# MicroBrute_Noise_add-on.net
KiCad netlist of a schematic drawn in EAGLE
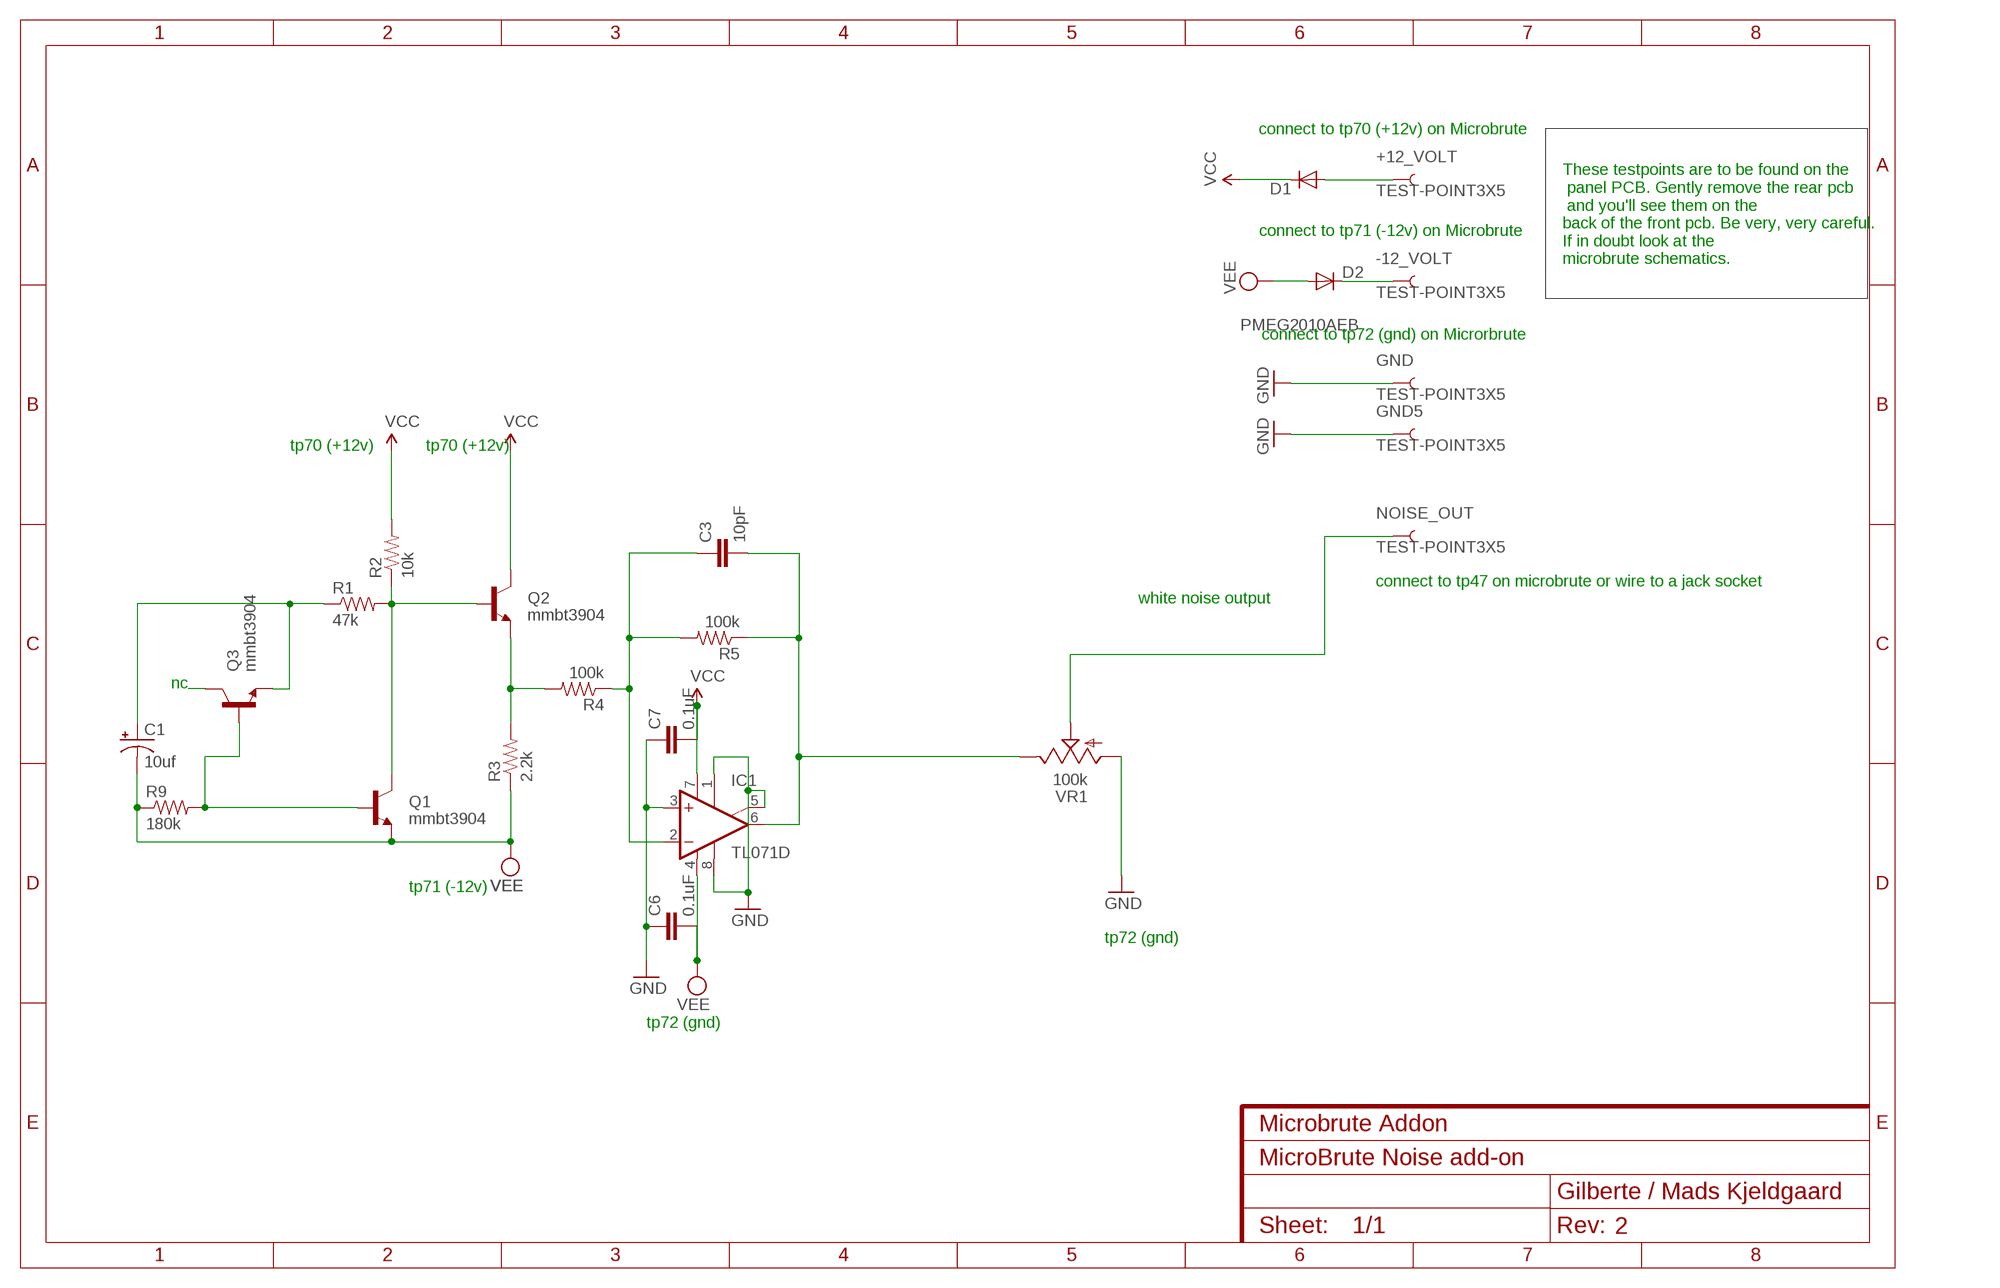
[diagram p0: schematic, sheet 1]

(export (version "E")
  (design (tool "Eeschema 10.0.6"))
  (components
    (comp (ref "+12_VOLT")
      (value "TEST-POINT3X5")
      (footprint "eagle-import:PAD.03X.05")
      (libsource (lib "eagle-import") (part "TEST-POINT3X5"))
    )
    (comp (ref "-12_VOLT")
      (value "TEST-POINT3X5")
      (footprint "eagle-import:PAD.03X.05")
      (libsource (lib "eagle-import") (part "TEST-POINT3X5"))
    )
    (comp (ref "C1")
      (value "10uf")
      (footprint "eagle-import:PANASONIC_C")
      (libsource (lib "eagle-import") (part "CAP_POLC"))
    )
    (comp (ref "C3")
      (value "10pF")
      (footprint "eagle-import:0603-CAP")
      (libsource (lib "eagle-import") (part "0.1UF-25V(+80/-20%)(0603)"))
    )
    (comp (ref "C6")
      (value "0.1uF")
      (footprint "eagle-import:0603-CAP")
      (libsource (lib "eagle-import") (part "0.1UF-25V(+80/-20%)(0603)"))
    )
    (comp (ref "C7")
      (value "0.1uF")
      (footprint "eagle-import:0603-CAP")
      (libsource (lib "eagle-import") (part "0.1UF-25V(+80/-20%)(0603)"))
    )
    (comp (ref "D1")
      (value "PMEG2010AEB")
      (footprint "eagle-import:SOD523")
      (libsource (lib "eagle-import") (part "DIODE-SOD523"))
    )
    (comp (ref "D2")
      (value "PMEG2010AEB")
      (footprint "eagle-import:SOD523")
      (libsource (lib "eagle-import") (part "DIODE-SOD523"))
    )
    (comp (ref "GND")
      (value "TEST-POINT3X5")
      (footprint "eagle-import:PAD.03X.05")
      (libsource (lib "eagle-import") (part "TEST-POINT3X5"))
    )
    (comp (ref "GND5")
      (value "TEST-POINT3X5")
      (footprint "eagle-import:PAD.03X.05")
      (libsource (lib "eagle-import") (part "TEST-POINT3X5"))
    )
    (comp (ref "IC1")
      (value "TL071D")
      (footprint "eagle-import:SO08")
      (libsource (lib "eagle-import") (part "TL071D"))
    )
    (comp (ref "NOISE_OUT")
      (value "TEST-POINT3X5")
      (footprint "eagle-import:PAD.03X.05")
      (libsource (lib "eagle-import") (part "TEST-POINT3X5"))
    )
    (comp (ref "Q1")
      (value "mmbt3904")
      (footprint "eagle-import:SOT23-3")
      (libsource (lib "eagle-import") (part "TRANSISTOR_NPNSOT23-3"))
    )
    (comp (ref "Q2")
      (value "mmbt3904")
      (footprint "eagle-import:SOT23-3")
      (libsource (lib "eagle-import") (part "TRANSISTOR_NPNSOT23-3"))
    )
    (comp (ref "Q3")
      (value "mmbt3904")
      (footprint "eagle-import:SOT23-3")
      (libsource (lib "eagle-import") (part "TRANSISTOR_NPNSOT23-3"))
    )
    (comp (ref "R1")
      (value "47k")
      (footprint "eagle-import:0603-RES")
      (libsource (lib "eagle-import") (part "RESISTOR0603-RES"))
    )
    (comp (ref "R2")
      (value "10k")
      (footprint "eagle-import:0603-RES")
      (libsource (lib "eagle-import") (part "RESISTOR0603-RES"))
    )
    (comp (ref "R3")
      (value "2.2k")
      (footprint "eagle-import:0603-RES")
      (libsource (lib "eagle-import") (part "RESISTOR0603-RES"))
    )
    (comp (ref "R4")
      (value "100k")
      (footprint "eagle-import:0603-RES")
      (libsource (lib "eagle-import") (part "RESISTOR0603-RES"))
    )
    (comp (ref "R5")
      (value "100k")
      (footprint "eagle-import:0603-RES")
      (libsource (lib "eagle-import") (part "RESISTOR0603-RES"))
    )
    (comp (ref "R9")
      (value "180k")
      (footprint "eagle-import:0603-RES")
      (libsource (lib "eagle-import") (part "RESISTOR0603-RES"))
    )
    (comp (ref "VR1")
      (value "100k")
      (footprint "eagle-import:9MM_SNAP-IN_POT")
      (libsource (lib "eagle-import") (part "9MM_SNAP-IN_POT_"))
    )
  )
  (nets
    (net (code "1") (name "GND") (class "Default")
      (node (ref "C6") (pin "1") (pinfunction "1_1") (pintype "passive"))
      (node (ref "C7") (pin "1") (pinfunction "1_1") (pintype "passive"))
      (node (ref "GND") (pin "P$1") (pinfunction "1_P$1") (pintype "bidirectional"))
      (node (ref "GND5") (pin "P$1") (pinfunction "1_P$1") (pintype "bidirectional"))
      (node (ref "IC1") (pin "1") (pinfunction "ON1_1") (pintype "passive"))
      (node (ref "IC1") (pin "3") (pinfunction "+IN_3") (pintype "input"))
      (node (ref "IC1") (pin "5") (pinfunction "ON2_5") (pintype "passive"))
      (node (ref "IC1") (pin "8") (pinfunction "OPT_8") (pintype "passive"))
      (node (ref "VR1") (pin "1") (pinfunction "A_1") (pintype "passive"))
    )
    (net (code "2") (name "Net-(+12_VOLT-1)") (class "Default")
      (node (ref "+12_VOLT") (pin "P$1") (pinfunction "1_P$1") (pintype "bidirectional"))
      (node (ref "D1") (pin "A") (pinfunction "A_A") (pintype "passive"))
    )
    (net (code "3") (name "Net-(-12_VOLT-1)") (class "Default")
      (node (ref "-12_VOLT") (pin "P$1") (pinfunction "1_P$1") (pintype "bidirectional"))
      (node (ref "D2") (pin "C") (pinfunction "C_C") (pintype "passive"))
    )
    (net (code "4") (name "Net-(IC1--IN)") (class "Default")
      (node (ref "C3") (pin "1") (pinfunction "1_1") (pintype "passive"))
      (node (ref "IC1") (pin "2") (pinfunction "-IN_2") (pintype "input"))
      (node (ref "R4") (pin "1") (pinfunction "1_1") (pintype "passive"))
      (node (ref "R5") (pin "2") (pinfunction "2_2") (pintype "passive"))
    )
    (net (code "5") (name "Net-(IC1-OUT)") (class "Default")
      (node (ref "C3") (pin "2") (pinfunction "2_2") (pintype "passive"))
      (node (ref "IC1") (pin "6") (pinfunction "OUT_6") (pintype "output"))
      (node (ref "R5") (pin "1") (pinfunction "1_1") (pintype "passive"))
      (node (ref "VR1") (pin "3") (pinfunction "E_3") (pintype "passive"))
    )
    (net (code "6") (name "Net-(NOISE_OUT-1)") (class "Default")
      (node (ref "NOISE_OUT") (pin "P$1") (pinfunction "1_P$1") (pintype "bidirectional"))
      (node (ref "VR1") (pin "2") (pinfunction "S_2") (pintype "passive"))
    )
    (net (code "7") (name "Net-(Q1-B)") (class "Default")
      (node (ref "Q1") (pin "1") (pinfunction "B_1") (pintype "passive"))
      (node (ref "Q3") (pin "1") (pinfunction "B_1") (pintype "passive"))
      (node (ref "R9") (pin "2") (pinfunction "2_2") (pintype "passive"))
    )
    (net (code "8") (name "Net-(Q1-C)") (class "Default")
      (node (ref "Q1") (pin "3") (pinfunction "C_3") (pintype "passive"))
      (node (ref "Q2") (pin "1") (pinfunction "B_1") (pintype "passive"))
      (node (ref "R1") (pin "2") (pinfunction "2_2") (pintype "passive"))
      (node (ref "R2") (pin "1") (pinfunction "1_1") (pintype "passive"))
    )
    (net (code "9") (name "Net-(Q2-E)") (class "Default")
      (node (ref "Q2") (pin "2") (pinfunction "E_2") (pintype "passive"))
      (node (ref "R3") (pin "2") (pinfunction "2_2") (pintype "passive"))
      (node (ref "R4") (pin "2") (pinfunction "2_2") (pintype "passive"))
    )
    (net (code "10") (name "Net-(Q3-E)") (class "Default")
      (node (ref "C1") (pin "+") (pinfunction "+_+") (pintype "passive"))
      (node (ref "Q3") (pin "2") (pinfunction "E_2") (pintype "passive"))
      (node (ref "R1") (pin "1") (pinfunction "1_1") (pintype "passive"))
    )
    (net (code "11") (name "VCC") (class "Default")
      (node (ref "C7") (pin "2") (pinfunction "2_2") (pintype "passive"))
      (node (ref "D1") (pin "C") (pinfunction "C_C") (pintype "passive"))
      (node (ref "IC1") (pin "7") (pinfunction "V+_7") (pintype "power_in"))
      (node (ref "Q2") (pin "3") (pinfunction "C_3") (pintype "passive"))
      (node (ref "R2") (pin "2") (pinfunction "2_2") (pintype "passive"))
    )
    (net (code "12") (name "VEE") (class "Default")
      (node (ref "C1") (pin "-") (pinfunction "-_-") (pintype "passive"))
      (node (ref "C6") (pin "2") (pinfunction "2_2") (pintype "passive"))
      (node (ref "D2") (pin "A") (pinfunction "A_A") (pintype "passive"))
      (node (ref "IC1") (pin "4") (pinfunction "V-_4") (pintype "power_in"))
      (node (ref "Q1") (pin "2") (pinfunction "E_2") (pintype "passive"))
      (node (ref "R3") (pin "1") (pinfunction "1_1") (pintype "passive"))
      (node (ref "R9") (pin "1") (pinfunction "1_1") (pintype "passive"))
    )
    (net (code "13") (name "unconnected-(Q3-C-Pad3)") (class "Default")
      (node (ref "Q3") (pin "3") (pinfunction "C_3") (pintype "passive"))
    )
  )
)
